# STM32_AUX.net
KiCad netlist of a schematic drawn in Altium Designer
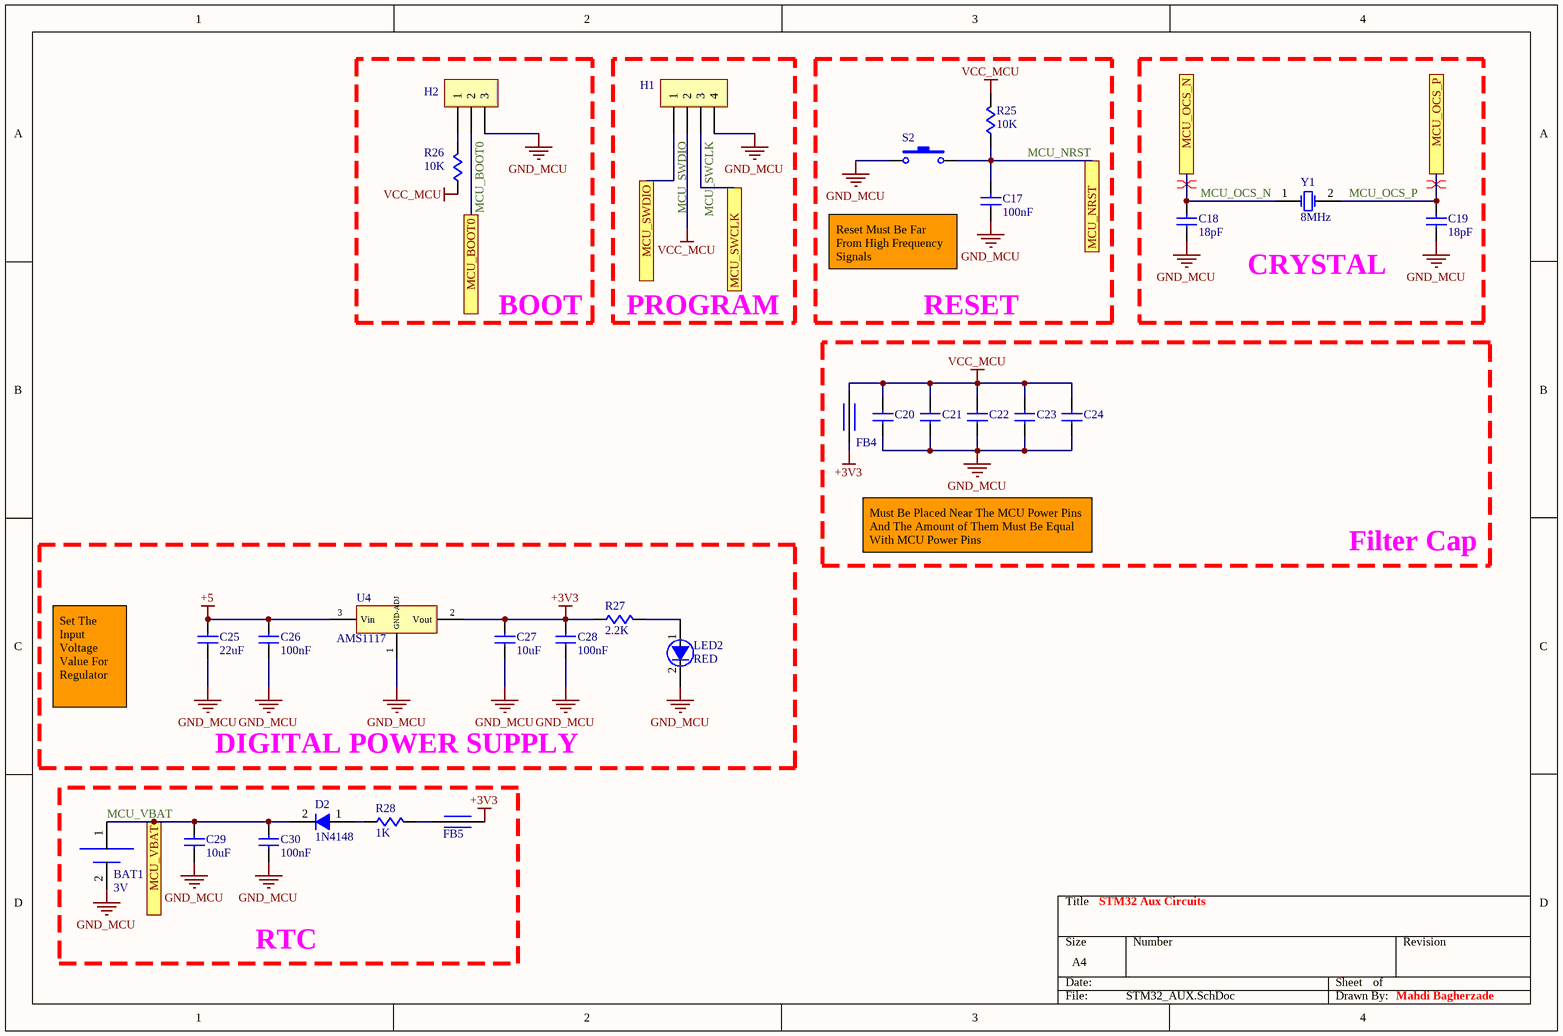
[diagram p0: STM32_AUX.SchDoc]

(export (version "E")
  (design (tool "Eeschema 10.0.6"))
  (components
    (comp (ref "BAT1")
      (value "Bat Holder 2016-SMD")
      (footprint "BAT-HOLDER-SMD-1220")
      (description "BATTERY")
      (fields (field (name "VOLTAGE") "3V") (field (name "PUBLISHER") "Mahdi Bagherzadeh"))
      (libsource (lib "Mahdi-Bagherzadeh") (part "BATTERY HOLDER"))
    )
    (comp (ref "C17")
      (value "100nF")
      (footprint "C-0805")
      (description "CAPACITOR")
      (fields
        (field (name "VOLTAGE") "50V")
        (field (name "TOLERANCE") "X7R")
        (field (name "PUBLISHER") "Mahdi Bagherzadeh")
      )
      (libsource (lib "Mahdi-Bagherzadeh") (part "CAP-CER"))
    )
    (comp (ref "C18")
      (value "18pF")
      (footprint "C-0805")
      (description "CAPACITOR")
      (fields
        (field (name "VOLTAGE") "50V")
        (field (name "TOLERANCE") "X7R")
        (field (name "PUBLISHER") "Mahdi Bagherzadeh")
      )
      (libsource (lib "Mahdi-Bagherzadeh") (part "CAP-CER"))
    )
    (comp (ref "C19")
      (value "18pF")
      (footprint "C-0805")
      (description "CAPACITOR")
      (fields
        (field (name "VOLTAGE") "50V")
        (field (name "TOLERANCE") "X7R")
        (field (name "PUBLISHER") "Mahdi Bagherzadeh")
      )
      (libsource (lib "Mahdi-Bagherzadeh") (part "CAP-CER"))
    )
    (comp (ref "C20")
      (value "CAP Cer 100nF-50V-X7R-SMD")
      (footprint "C-0805")
      (description "CAPACITOR")
      (fields
        (field (name "VOLTAGE") "50V")
        (field (name "TOLERANCE") "X7R")
        (field (name "PUBLISHER") "Mahdi Bagherzadeh")
      )
      (libsource (lib "Mahdi-Bagherzadeh") (part "CAP-CER"))
    )
    (comp (ref "C21")
      (value "CAP Cer 100nF-50V-X7R-SMD")
      (footprint "C-0805")
      (description "CAPACITOR")
      (fields
        (field (name "VOLTAGE") "50V")
        (field (name "TOLERANCE") "X7R")
        (field (name "PUBLISHER") "Mahdi Bagherzadeh")
      )
      (libsource (lib "Mahdi-Bagherzadeh") (part "CAP-CER"))
    )
    (comp (ref "C22")
      (value "CAP Cer 100nF-50V-X7R-SMD")
      (footprint "C-0805")
      (description "CAPACITOR")
      (fields
        (field (name "VOLTAGE") "50V")
        (field (name "TOLERANCE") "X7R")
        (field (name "PUBLISHER") "Mahdi Bagherzadeh")
      )
      (libsource (lib "Mahdi-Bagherzadeh") (part "CAP-CER"))
    )
    (comp (ref "C23")
      (value "CAP Cer 100nF-50V-X7R-SMD")
      (footprint "C-0805")
      (description "CAPACITOR")
      (fields
        (field (name "VOLTAGE") "50V")
        (field (name "TOLERANCE") "X7R")
        (field (name "PUBLISHER") "Mahdi Bagherzadeh")
      )
      (libsource (lib "Mahdi-Bagherzadeh") (part "CAP-CER"))
    )
    (comp (ref "C24")
      (value "CAP Cer 100nF-50V-X7R-SMD")
      (footprint "C-0805")
      (description "CAPACITOR")
      (fields
        (field (name "VOLTAGE") "50V")
        (field (name "TOLERANCE") "X7R")
        (field (name "PUBLISHER") "Mahdi Bagherzadeh")
      )
      (libsource (lib "Mahdi-Bagherzadeh") (part "CAP-CER"))
    )
    (comp (ref "C25")
      (value "22uF")
      (footprint "C-0805")
      (description "CAPACITOR")
      (fields
        (field (name "VOLTAGE") "50V")
        (field (name "TOLERANCE") "X7R")
        (field (name "PUBLISHER") "Mahdi Bagherzadeh")
      )
      (libsource (lib "Mahdi-Bagherzadeh") (part "CAP-CER"))
    )
    (comp (ref "C26")
      (value "100nF")
      (footprint "C-0805")
      (description "CAPACITOR")
      (fields
        (field (name "VOLTAGE") "50V")
        (field (name "TOLERANCE") "X7R")
        (field (name "PUBLISHER") "Mahdi Bagherzadeh")
      )
      (libsource (lib "Mahdi-Bagherzadeh") (part "CAP-CER"))
    )
    (comp (ref "C27")
      (value "10uF")
      (footprint "C-0805")
      (description "CAPACITOR")
      (fields
        (field (name "VOLTAGE") "50V")
        (field (name "TOLERANCE") "X7R")
        (field (name "PUBLISHER") "Mahdi Bagherzadeh")
      )
      (libsource (lib "Mahdi-Bagherzadeh") (part "CAP-CER"))
    )
    (comp (ref "C28")
      (value "100nF")
      (footprint "C-0805")
      (description "CAPACITOR")
      (fields
        (field (name "VOLTAGE") "50V")
        (field (name "TOLERANCE") "X7R")
        (field (name "PUBLISHER") "Mahdi Bagherzadeh")
      )
      (libsource (lib "Mahdi-Bagherzadeh") (part "CAP-CER"))
    )
    (comp (ref "C29")
      (value "10uF")
      (footprint "C-0805")
      (description "CAPACITOR")
      (fields
        (field (name "VOLTAGE") "50V")
        (field (name "TOLERANCE") "X7R")
        (field (name "PUBLISHER") "Mahdi Bagherzadeh")
      )
      (libsource (lib "Mahdi-Bagherzadeh") (part "CAP-CER"))
    )
    (comp (ref "C30")
      (value "100nF")
      (footprint "C-0805")
      (description "CAPACITOR")
      (fields
        (field (name "VOLTAGE") "50V")
        (field (name "TOLERANCE") "X7R")
        (field (name "PUBLISHER") "Mahdi Bagherzadeh")
      )
      (libsource (lib "Mahdi-Bagherzadeh") (part "CAP-CER"))
    )
    (comp (ref "D2")
      (value "Diode 1N4148-SMD")
      (footprint "SOD80")
      (description "DIODE")
      (fields (field (name "CODE") "1N4148") (field (name "PUBLISHER") "Mahdi Bagherzadeh"))
      (libsource (lib "Mahdi-Bagherzadeh") (part "DIODE"))
    )
    (comp (ref "FB4")
      (value "FERRITE BEAD")
      (footprint "FB-0805")
      (description "INDUCATOR")
      (fields (field (name "PUBLISHER") "Mahdi Bagherzadeh"))
      (libsource (lib "Mahdi-Bagherzadeh") (part "FERRITE BEAD"))
    )
    (comp (ref "FB5")
      (value "Ferrite Bead SMD")
      (footprint "FB-0805")
      (description "INDUCATOR")
      (fields (field (name "PUBLISHER") "Mahdi Bagherzadeh"))
      (libsource (lib "Mahdi-Bagherzadeh") (part "FERRITE BEAD"))
    )
    (comp (ref "H1")
      (value "Header 4x1 Pin -Straight-Male-2.54mm")
      (footprint "H-4pin-M-S")
      (description "HEADER")
      (fields (field (name "PUBLISHER") "Mahdi Bagherzadeh"))
      (libsource (lib "Mahdi-Bagherzadeh") (part "HEADER-4pin"))
    )
    (comp (ref "H2")
      (value "Header 3x1 Pin -Straight-Male-2.54mm")
      (footprint "H-3pin-M-S")
      (description "HEADER")
      (fields (field (name "PUBLISHER") "Mahdi Bagherzadeh"))
      (libsource (lib "Mahdi-Bagherzadeh") (part "HEADER-3pin"))
    )
    (comp (ref "LED2")
      (value "LED RED-1206-SMD")
      (footprint "LED-1206-R")
      (description "LED")
      (fields (field (name "COLOR") "RED") (field (name "PUBLISHER") "Mahdi Bagherzadeh"))
      (libsource (lib "Mahdi-Bagherzadeh") (part "LED"))
    )
    (comp (ref "R25")
      (value "10K")
      (footprint "R-0805")
      (description "RESISTOR")
      (fields
        (field (name "TOLERANCE") "5%")
        (field (name "POWER") "1/8W")
        (field (name "PUBLISHER") "Mahdi Bagherzadeh")
      )
      (libsource (lib "Mahdi-Bagherzadeh") (part "RES"))
    )
    (comp (ref "R26")
      (value "10K")
      (footprint "R-0805")
      (description "RESISTOR")
      (fields
        (field (name "TOLERANCE") "5%")
        (field (name "POWER") "1/8W")
        (field (name "PUBLISHER") "Mahdi Bagherzadeh")
      )
      (libsource (lib "Mahdi-Bagherzadeh") (part "RES"))
    )
    (comp (ref "R27")
      (value "2.2K")
      (footprint "R-0805")
      (description "RESISTOR")
      (fields
        (field (name "TOLERANCE") "5%")
        (field (name "POWER") "1/8W")
        (field (name "PUBLISHER") "Mahdi Bagherzadeh")
      )
      (libsource (lib "Mahdi-Bagherzadeh") (part "RES"))
    )
    (comp (ref "R28")
      (value "1K")
      (footprint "R-0805")
      (description "RESISTOR")
      (fields
        (field (name "TOLERANCE") "5%")
        (field (name "POWER") "1/8W")
        (field (name "PUBLISHER") "Mahdi Bagherzadeh")
      )
      (libsource (lib "Mahdi-Bagherzadeh") (part "RES"))
    )
    (comp (ref "S2")
      (value "Push Button 3x6mm-2Pin-SMD")
      (footprint "SW-SMD-2pin-3x6")
      (description "SWITCH")
      (fields (field (name "PUBLISHER") "Mahdi Bagherzadeh"))
      (libsource (lib "Mahdi-Bagherzadeh") (part "PUSH BUTTON"))
    )
    (comp (ref "U4")
      (value "Reg AMS1117-3.3V-SMD")
      (footprint "SOT223")
      (description "REGULATOR")
      (fields
        (field (name "VOLTAGE") "3.3V")
        (field (name "CODE") "AMS1117")
        (field (name "PUBLISHER") "Mahdi Bagherzadeh")
      )
      (libsource (lib "Mahdi-Bagherzadeh") (part "AMS1117"))
    )
    (comp (ref "Y1")
      (value "8MHz")
      (footprint "CRYSTAL-SMD")
      (description "CRYSTAL")
      (fields (field (name "Comment") "Crystal 8MHz-SMD") (field (name "PUBLISHER") "Mahdi Bagherzadeh"))
      (libsource (lib "Mahdi-Bagherzadeh") (part "CRYSTAL"))
    )
  )
  (nets
    (net (code "1") (name "+3V3") (class "Default")
      (node (ref "C27") (pin "2") (pinfunction "2_2") (pintype "passive"))
      (node (ref "C28") (pin "2") (pinfunction "2_2") (pintype "passive"))
      (node (ref "FB4") (pin "1") (pinfunction "1_1") (pintype "passive"))
      (node (ref "FB5") (pin "1") (pinfunction "1_1") (pintype "passive"))
      (node (ref "R27") (pin "1") (pinfunction "1_1") (pintype "passive"))
      (node (ref "U4") (pin "2") (pinfunction "Vout_2") (pintype "power_in"))
    )
    (net (code "2") (name "+5") (class "Default")
      (node (ref "C25") (pin "2") (pinfunction "2_2") (pintype "passive"))
      (node (ref "C26") (pin "2") (pinfunction "2_2") (pintype "passive"))
      (node (ref "U4") (pin "3") (pinfunction "Vin_3") (pintype "power_in"))
    )
    (net (code "3") (name "/MCU_BOOT0") (class "Default")
      (node (ref "H2") (pin "2") (pinfunction "2_2") (pintype "passive"))
    )
    (net (code "4") (name "/MCU_NRST") (class "Default")
      (node (ref "C17") (pin "2") (pinfunction "2_2") (pintype "passive"))
      (node (ref "R25") (pin "1") (pinfunction "1_1") (pintype "passive"))
      (node (ref "S2") (pin "2") (pinfunction "2_2") (pintype "passive"))
    )
    (net (code "5") (name "/MCU_OCS_N") (class "Default")
      (node (ref "C18") (pin "2") (pinfunction "2_2") (pintype "passive"))
      (node (ref "Y1") (pin "1") (pinfunction "OSC1_1") (pintype "passive"))
    )
    (net (code "6") (name "/MCU_OCS_P") (class "Default")
      (node (ref "C19") (pin "2") (pinfunction "2_2") (pintype "passive"))
      (node (ref "Y1") (pin "2") (pinfunction "OSC2_2") (pintype "passive"))
    )
    (net (code "7") (name "/MCU_SWCLK") (class "Default")
      (node (ref "H1") (pin "3") (pinfunction "3_3") (pintype "passive"))
    )
    (net (code "8") (name "/MCU_SWDIO") (class "Default")
      (node (ref "H1") (pin "1") (pinfunction "1_1") (pintype "passive"))
    )
    (net (code "9") (name "/MCU_VBAT") (class "Default")
      (node (ref "BAT1") (pin "1") (pinfunction "+_1") (pintype "passive"))
      (node (ref "C29") (pin "2") (pinfunction "2_2") (pintype "passive"))
      (node (ref "C30") (pin "2") (pinfunction "2_2") (pintype "passive"))
      (node (ref "D2") (pin "2") (pinfunction "C_2") (pintype "passive"))
    )
    (net (code "10") (name "GND_MCU") (class "Default")
      (node (ref "BAT1") (pin "2") (pinfunction "-_2") (pintype "passive"))
      (node (ref "C17") (pin "1") (pinfunction "1_1") (pintype "passive"))
      (node (ref "C18") (pin "1") (pinfunction "1_1") (pintype "passive"))
      (node (ref "C19") (pin "1") (pinfunction "1_1") (pintype "passive"))
      (node (ref "C20") (pin "2") (pinfunction "2_2") (pintype "passive"))
      (node (ref "C21") (pin "2") (pinfunction "2_2") (pintype "passive"))
      (node (ref "C22") (pin "2") (pinfunction "2_2") (pintype "passive"))
      (node (ref "C23") (pin "2") (pinfunction "2_2") (pintype "passive"))
      (node (ref "C24") (pin "2") (pinfunction "2_2") (pintype "passive"))
      (node (ref "C25") (pin "1") (pinfunction "1_1") (pintype "passive"))
      (node (ref "C26") (pin "1") (pinfunction "1_1") (pintype "passive"))
      (node (ref "C27") (pin "1") (pinfunction "1_1") (pintype "passive"))
      (node (ref "C28") (pin "1") (pinfunction "1_1") (pintype "passive"))
      (node (ref "C29") (pin "1") (pinfunction "1_1") (pintype "passive"))
      (node (ref "C30") (pin "1") (pinfunction "1_1") (pintype "passive"))
      (node (ref "H1") (pin "4") (pinfunction "4_4") (pintype "passive"))
      (node (ref "H2") (pin "3") (pinfunction "3_3") (pintype "passive"))
      (node (ref "LED2") (pin "2") (pinfunction "C_2") (pintype "passive"))
      (node (ref "S2") (pin "1") (pinfunction "1_1") (pintype "passive"))
      (node (ref "U4") (pin "1") (pinfunction "GND-ADJ_1") (pintype "power_in"))
    )
    (net (code "11") (name "Net-(D2-A)") (class "Default")
      (node (ref "D2") (pin "1") (pinfunction "A_1") (pintype "passive"))
      (node (ref "R28") (pin "1") (pinfunction "1_1") (pintype "passive"))
    )
    (net (code "12") (name "Net-(FB5-Pad2)") (class "Default")
      (node (ref "FB5") (pin "2") (pinfunction "2_2") (pintype "passive"))
      (node (ref "R28") (pin "2") (pinfunction "2_2") (pintype "passive"))
    )
    (net (code "13") (name "Net-(H2-Pad1)") (class "Default")
      (node (ref "H2") (pin "1") (pinfunction "1_1") (pintype "passive"))
      (node (ref "R26") (pin "2") (pinfunction "2_2") (pintype "passive"))
    )
    (net (code "14") (name "Net-(LED2-A)") (class "Default")
      (node (ref "LED2") (pin "1") (pinfunction "A_1") (pintype "passive"))
      (node (ref "R27") (pin "2") (pinfunction "2_2") (pintype "passive"))
    )
    (net (code "15") (name "VCC_MCU") (class "Default")
      (node (ref "C20") (pin "1") (pinfunction "1_1") (pintype "passive"))
      (node (ref "C21") (pin "1") (pinfunction "1_1") (pintype "passive"))
      (node (ref "C22") (pin "1") (pinfunction "1_1") (pintype "passive"))
      (node (ref "C23") (pin "1") (pinfunction "1_1") (pintype "passive"))
      (node (ref "C24") (pin "1") (pinfunction "1_1") (pintype "passive"))
      (node (ref "FB4") (pin "2") (pinfunction "2_2") (pintype "passive"))
      (node (ref "H1") (pin "2") (pinfunction "2_2") (pintype "passive"))
      (node (ref "R25") (pin "2") (pinfunction "2_2") (pintype "passive"))
      (node (ref "R26") (pin "1") (pinfunction "1_1") (pintype "passive"))
    )
  )
)
